# Amplifier.net
KiCad netlist of a schematic drawn in Altium Designer
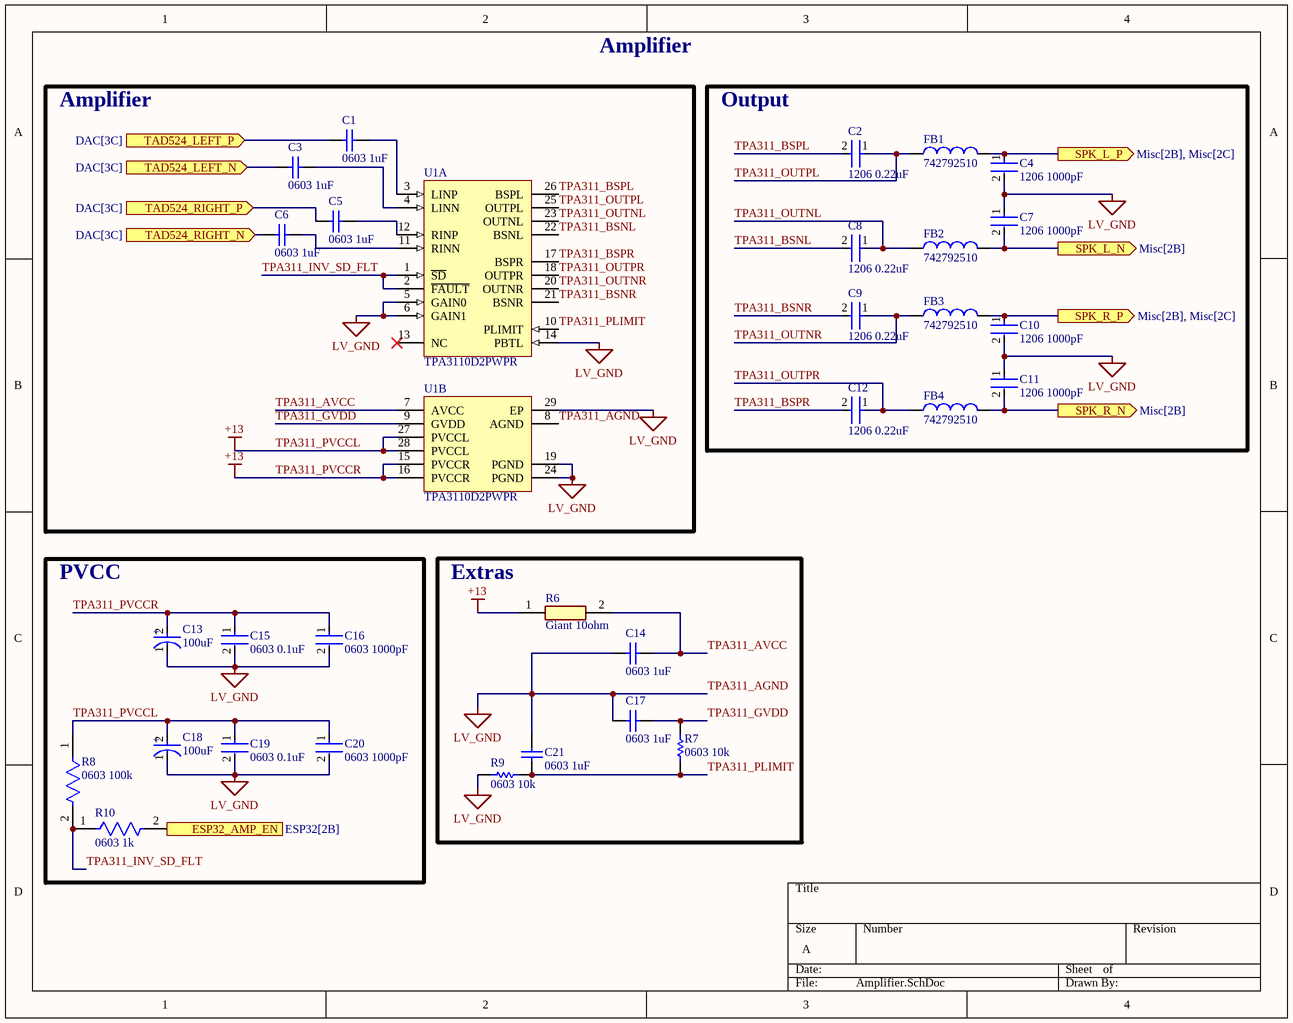
[diagram p0: Amplifier.SchDoc]

(export (version "E")
  (design (tool "Eeschema 10.0.6"))
  (components
    (comp (ref "C1")
      (value "0603 1uF")
      (footprint "CAPC1608X87X35LL15T15")
      (fields (field (name "PART NUMBER") "C0603C105K3RACTU") (field (name "MANUFACTURER") "Kemet"))
      (libsource (lib "Altium Content Vault") (part "CAP"))
    )
    (comp (ref "C2")
      (value "1206 0.22uF")
      (footprint "FP-C1206C-EB-MFG")
      (description "CAP CER 0.22UF 50V X7R 1206")
      (fields
        (field (name "OCTOPART") "https://octopart.com/c1206c224k5ractu-kemet-99129")
        (field (name "MANUFACTURER PART NUMBER") "C1206C224K5RACTU")
      )
      (libsource (lib "Altium Content Vault") (part "b4654b650e69147ec39a6b967a45e02"))
    )
    (comp (ref "C3")
      (value "0603 1uF")
      (footprint "CAPC1608X87X35LL15T15")
      (fields (field (name "PART NUMBER") "C0603C105K3RACTU") (field (name "MANUFACTURER") "Kemet"))
      (libsource (lib "Altium Content Vault") (part "CAP"))
    )
    (comp (ref "C4")
      (value "1206 1000pF")
      (footprint "FP-C1206C-EB-MFG")
      (description "CAP CER 100PF 100V C0G/NP0 1206")
      (fields (field (name "MANUFACTURER") "KEMET") (field (name "TOLERANCE") "0.05"))
      (libsource (lib "Altium Content Vault") (part "b4654b650e69147ec39a6b967a45e02"))
    )
    (comp (ref "C5")
      (value "0603 1uF")
      (footprint "CAPC1608X87X35LL15T15")
      (fields (field (name "PART NUMBER") "C0603C105K3RACTU") (field (name "MANUFACTURER") "Kemet"))
      (libsource (lib "Altium Content Vault") (part "CAP"))
    )
    (comp (ref "C6")
      (value "0603 1uF")
      (footprint "CAPC1608X87X35LL15T15")
      (fields (field (name "PART NUMBER") "C0603C105K3RACTU") (field (name "MANUFACTURER") "Kemet"))
      (libsource (lib "Altium Content Vault") (part "CAP"))
    )
    (comp (ref "C7")
      (value "1206 1000pF")
      (footprint "FP-C1206C-EB-MFG")
      (description "CAP CER 100PF 100V C0G/NP0 1206")
      (fields (field (name "MANUFACTURER") "KEMET") (field (name "TOLERANCE") "0.05"))
      (libsource (lib "Altium Content Vault") (part "b4654b650e69147ec39a6b967a45e02"))
    )
    (comp (ref "C8")
      (value "1206 0.22uF")
      (footprint "FP-C1206C-EB-MFG")
      (description "CAP CER 0.22UF 50V X7R 1206")
      (fields
        (field (name "OCTOPART") "https://octopart.com/c1206c224k5ractu-kemet-99129")
        (field (name "MANUFACTURER PART NUMBER") "C1206C224K5RACTU")
      )
      (libsource (lib "Altium Content Vault") (part "b4654b650e69147ec39a6b967a45e02"))
    )
    (comp (ref "C9")
      (value "1206 0.22uF")
      (footprint "FP-C1206C-EB-MFG")
      (description "CAP CER 0.22UF 50V X7R 1206")
      (fields
        (field (name "OCTOPART") "https://octopart.com/c1206c224k5ractu-kemet-99129")
        (field (name "MANUFACTURER PART NUMBER") "C1206C224K5RACTU")
      )
      (libsource (lib "Altium Content Vault") (part "b4654b650e69147ec39a6b967a45e02"))
    )
    (comp (ref "C10")
      (value "1206 1000pF")
      (footprint "FP-C1206C-EB-MFG")
      (description "CAP CER 100PF 100V C0G/NP0 1206")
      (fields (field (name "MANUFACTURER") "KEMET") (field (name "TOLERANCE") "0.05"))
      (libsource (lib "Altium Content Vault") (part "b4654b650e69147ec39a6b967a45e02"))
    )
    (comp (ref "C11")
      (value "1206 1000pF")
      (footprint "FP-C1206C-EB-MFG")
      (description "CAP CER 100PF 100V C0G/NP0 1206\r\nC1206C101J1GACTU")
      (fields (field (name "MANUFACTURER") "KEMET") (field (name "TOLERANCE") "0.05"))
      (libsource (lib "Altium Content Vault") (part "b4654b650e69147ec39a6b967a45e02"))
    )
    (comp (ref "C12")
      (value "1206 0.22uF")
      (footprint "FP-C1206C-EB-MFG")
      (description "CAP CER 0.22UF 50V X7R 1206")
      (fields
        (field (name "OCTOPART") "https://octopart.com/c1206c224k5ractu-kemet-99129")
        (field (name "MANUFACTURER PART NUMBER") "C1206C224K5RACTU")
      )
      (libsource (lib "Altium Content Vault") (part "b4654b650e69147ec39a6b967a45e02"))
    )
    (comp (ref "C13")
      (value "100uF")
      (footprint "FP-RAD-TH-D_8_0_5-L_11_5-MFG")
      (description "Aluminum Electrolytic Capacitors (Radial Lead Type) 100uF ±20% 50V")
      (fields (field (name "VOLTAGE") "50V") (field (name "TOLERANCE") "20%"))
      (libsource (lib "Altium Content Vault") (part "a00bbbee19879c290e62620ae7e47b1"))
    )
    (comp (ref "C14")
      (value "0603 1uF")
      (footprint "CAPC1608X87X35LL15T15")
      (fields (field (name "PART NUMBER") "C0603C105K3RACTU") (field (name "MANUFACTURER") "Kemet"))
      (libsource (lib "Altium Content Vault") (part "CAP"))
    )
    (comp (ref "C15")
      (value "0603 0.1uF")
      (footprint "FP-C0603C-CF-MFG")
      (description "CAP CER 0.1UF 25V X7R 0603")
      (fields
        (field (name "MANUFACTURER PART NUMBER") "C0603C104K3RACTU")
        (field (name "OCTOPART") "https://octopart.com/c0603c104k3ractu-kemet-127541")
      )
      (libsource (lib "Altium Content Vault") (part "b4654b650e69147ec39a6b967a45e02"))
    )
    (comp (ref "C16")
      (value "0603 1000pF")
      (footprint "FP-C0603C-CF-MFG")
      (description "CAP CER 1000PF 25V 5% NP0 0603")
      (fields
        (field (name "OCTOPART") "https://octopart.com/c0603c102j3gactu-kemet-8375722")
        (field (name "TOLERANCE") "0.05")
      )
      (libsource (lib "Altium Content Vault") (part "b4654b650e69147ec39a6b967a45e02"))
    )
    (comp (ref "C17")
      (value "0603 1uF")
      (footprint "CAPC1608X87X35LL15T15")
      (fields (field (name "PART NUMBER") "C0603C105K3RACTU") (field (name "MANUFACTURER") "Kemet"))
      (libsource (lib "Altium Content Vault") (part "CAP"))
    )
    (comp (ref "C18")
      (value "100uF")
      (footprint "FP-RAD-TH-D_8_0_5-L_11_5-MFG")
      (description "Aluminum Electrolytic Capacitors (Radial Lead Type) 100uF ±20% 50V")
      (fields (field (name "VOLTAGE") "50V") (field (name "TOLERANCE") "20%"))
      (libsource (lib "Altium Content Vault") (part "a00bbbee19879c290e62620ae7e47b1"))
    )
    (comp (ref "C19")
      (value "0603 0.1uF")
      (footprint "FP-C0603C-CF-MFG")
      (description "CAP CER 0.1UF 25V X7R 0603")
      (fields
        (field (name "MANUFACTURER PART NUMBER") "C0603C104K3RACTU")
        (field (name "OCTOPART") "https://octopart.com/c0603c104k3ractu-kemet-127541")
      )
      (libsource (lib "Altium Content Vault") (part "b4654b650e69147ec39a6b967a45e02"))
    )
    (comp (ref "C20")
      (value "0603 1000pF")
      (footprint "FP-C0603C-CF-MFG")
      (description "CAP CER 1000PF 25V 5% NP0 0603")
      (fields
        (field (name "OCTOPART") "https://octopart.com/c0603c102j3gactu-kemet-8375722")
        (field (name "TOLERANCE") "0.05")
      )
      (libsource (lib "Altium Content Vault") (part "b4654b650e69147ec39a6b967a45e02"))
    )
    (comp (ref "C21")
      (value "0603 1uF")
      (footprint "CAPC1608X87X35LL15T15")
      (fields (field (name "PART NUMBER") "C0603C105K3RACTU") (field (name "MANUFACTURER") "Kemet"))
      (libsource (lib "Altium Content Vault") (part "CAP"))
    )
    (comp (ref "FB1")
      (value "742792510")
      (footprint "WE-CBF_1812_L4.5W3.2H1.5_HC")
      (fields (field (name "TOLERANCE") "25%"))
      (libsource (lib "Altium Content Vault") (part "Ferrite"))
    )
    (comp (ref "FB2")
      (value "742792510")
      (footprint "WE-CBF_1812_L4.5W3.2H1.5_HC")
      (fields (field (name "TOLERANCE") "25%"))
      (libsource (lib "Altium Content Vault") (part "Ferrite"))
    )
    (comp (ref "FB3")
      (value "742792510")
      (footprint "WE-CBF_1812_L4.5W3.2H1.5_HC")
      (fields (field (name "TOLERANCE") "25%"))
      (libsource (lib "Altium Content Vault") (part "Ferrite"))
    )
    (comp (ref "FB4")
      (value "742792510")
      (footprint "WE-CBF_1812_L4.5W3.2H1.5_HC")
      (fields (field (name "TOLERANCE") "25%"))
      (libsource (lib "Altium Content Vault") (part "Ferrite"))
    )
    (comp (ref "R6")
      (value "Giant 10ohm")
      (footprint "SamacSys:TO508P350X1040X2030-2P")
      (description "Resistor")
      (fields
        (field (name "MANUFACTURER_PART_NUMBER") "LTO050F10R00JTE3")
        (field (name "MOUSER PART NUMBER") "72-LTO050F10R00JTE3")
      )
      (libsource (lib "*") (part "LTO050F10R00JTE3"))
    )
    (comp (ref "R7")
      (value "0603 10k")
      (footprint "RESC1609X55X30LL15T15")
      (description "Chip Resistor, 10 KOhm, +/- 1%, 0.1 W, -55 to 155 degC, 0603 (1608 Metric), RoHS, Tape and Reel")
      (fields (field (name "TOLERANCE") "1%") (field (name "MANUFACTURER") "Panasonic"))
      (libsource (lib "Altium Content Vault") (part "RES-2"))
    )
    (comp (ref "R8")
      (value "0603 100k")
      (footprint "FP-RC0603-0_55-MFG")
      (description "RES SMD 100K OHM 1% 1/10W 0603")
      (fields (field (name "TOLERANCE") "1%"))
      (libsource (lib "Altium Content Vault") (part "1029c3af85768c4190bb7ad29bc67b5"))
    )
    (comp (ref "R9")
      (value "0603 10k")
      (footprint "RESC1609X55X30LL15T15")
      (description "Chip Resistor, 10 KOhm, +/- 1%, 0.1 W, -55 to 155 degC, 0603 (1608 Metric), RoHS, Tape and Reel")
      (fields (field (name "TOLERANCE") "1%") (field (name "MANUFACTURER") "Panasonic"))
      (libsource (lib "Altium Content Vault") (part "RES-2"))
    )
    (comp (ref "R10")
      (value "0603 1k")
      (footprint "FP-AC0603-IPC_B")
      (description "RES 1kΩ 1.00% 0.1W 0603")
      (fields (field (name "TOLERANCE") "1%"))
      (libsource (lib "Altium Content Vault") (part "1029c3af85768c4190bb7ad29bc67b5"))
    )
    (comp (ref "U1")
      (value "TPA3110D2PWPR")
      (footprint "TI-PWP28-5720X1950TP_L")
      (fields (field (name "MANUFACTURER") "Texas Instruments"))
      (libsource (lib "Altium Content Vault") (part "TI-TPA311XD2PWP28-6240X1950TP"))
    )
  )
  (nets
    (net (code "1") (name "+13") (class "Default")
      (node (ref "C13") (pin "2") (pinfunction "A_2") (pintype "passive"))
      (node (ref "C15") (pin "1") (pinfunction "1_1") (pintype "passive"))
      (node (ref "C16") (pin "1") (pinfunction "1_1") (pintype "passive"))
      (node (ref "C18") (pin "2") (pinfunction "A_2") (pintype "passive"))
      (node (ref "C19") (pin "1") (pinfunction "1_1") (pintype "passive"))
      (node (ref "C20") (pin "1") (pinfunction "1_1") (pintype "passive"))
      (node (ref "R6") (pin "1") (pinfunction "1_1") (pintype "passive"))
      (node (ref "R8") (pin "1") (pinfunction "1_1") (pintype "passive"))
      (node (ref "U1") (pin "15") (pinfunction "PVCCR_15") (pintype "power_in"))
      (node (ref "U1") (pin "16") (pinfunction "PVCCR_16") (pintype "power_in"))
      (node (ref "U1") (pin "27") (pinfunction "PVCCL_27") (pintype "power_in"))
      (node (ref "U1") (pin "28") (pinfunction "PVCCL_28") (pintype "power_in"))
    )
    (net (code "2") (name "/ESP32_AMP_EN") (class "Default")
      (node (ref "R10") (pin "2") (pinfunction "2_2") (pintype "passive"))
    )
    (net (code "3") (name "/SPK_L_N") (class "Default")
      (node (ref "C7") (pin "2") (pinfunction "2_2") (pintype "passive"))
      (node (ref "FB2") (pin "2") (pinfunction "2_2") (pintype "passive"))
    )
    (net (code "4") (name "/SPK_L_P") (class "Default")
      (node (ref "C4") (pin "1") (pinfunction "1_1") (pintype "passive"))
      (node (ref "FB1") (pin "2") (pinfunction "2_2") (pintype "passive"))
    )
    (net (code "5") (name "/SPK_R_N") (class "Default")
      (node (ref "C11") (pin "2") (pinfunction "2_2") (pintype "passive"))
      (node (ref "FB4") (pin "2") (pinfunction "2_2") (pintype "passive"))
    )
    (net (code "6") (name "/SPK_R_P") (class "Default")
      (node (ref "C10") (pin "1") (pinfunction "1_1") (pintype "passive"))
      (node (ref "FB3") (pin "2") (pinfunction "2_2") (pintype "passive"))
    )
    (net (code "7") (name "/TAD524_LEFT_N") (class "Default")
      (node (ref "C3") (pin "1") (pinfunction "1_1") (pintype "passive"))
    )
    (net (code "8") (name "/TAD524_LEFT_P") (class "Default")
      (node (ref "C1") (pin "1") (pinfunction "1_1") (pintype "passive"))
    )
    (net (code "9") (name "/TAD524_RIGHT_N") (class "Default")
      (node (ref "C6") (pin "1") (pinfunction "1_1") (pintype "passive"))
    )
    (net (code "10") (name "/TAD524_RIGHT_P") (class "Default")
      (node (ref "C5") (pin "1") (pinfunction "1_1") (pintype "passive"))
    )
    (net (code "11") (name "/TPA311_AVCC") (class "Default")
      (node (ref "C14") (pin "2") (pinfunction "2_2") (pintype "passive"))
      (node (ref "R6") (pin "2") (pinfunction "2_2") (pintype "passive"))
      (node (ref "U1") (pin "7") (pinfunction "AVCC_7") (pintype "power_in"))
    )
    (net (code "12") (name "/TPA311_BSNL") (class "Default")
      (node (ref "C8") (pin "2") (pinfunction "2_2") (pintype "passive"))
      (node (ref "U1") (pin "22") (pinfunction "BSNL_22") (pintype "passive"))
    )
    (net (code "13") (name "/TPA311_BSNR") (class "Default")
      (node (ref "C9") (pin "2") (pinfunction "2_2") (pintype "passive"))
      (node (ref "U1") (pin "21") (pinfunction "BSNR_21") (pintype "passive"))
    )
    (net (code "14") (name "/TPA311_BSPL") (class "Default")
      (node (ref "C2") (pin "2") (pinfunction "2_2") (pintype "passive"))
      (node (ref "U1") (pin "26") (pinfunction "BSPL_26") (pintype "passive"))
    )
    (net (code "15") (name "/TPA311_BSPR") (class "Default")
      (node (ref "C12") (pin "2") (pinfunction "2_2") (pintype "passive"))
      (node (ref "U1") (pin "17") (pinfunction "BSPR_17") (pintype "passive"))
    )
    (net (code "16") (name "/TPA311_GVDD") (class "Default")
      (node (ref "C17") (pin "2") (pinfunction "2_2") (pintype "passive"))
      (node (ref "R7") (pin "1") (pinfunction "1_1") (pintype "passive"))
      (node (ref "U1") (pin "9") (pinfunction "GVDD_9") (pintype "power_in"))
    )
    (net (code "17") (name "/TPA311_INV_SD_FLT") (class "Default")
      (node (ref "R10") (pin "1") (pinfunction "1_1") (pintype "passive"))
      (node (ref "R8") (pin "2") (pinfunction "2_2") (pintype "passive"))
      (node (ref "U1") (pin "1") (pinfunction "~{SD}_1") (pintype "input"))
      (node (ref "U1") (pin "2") (pinfunction "~{FAULT}_2") (pintype "open_collector"))
    )
    (net (code "18") (name "/TPA311_OUTNL") (class "Default")
      (node (ref "C8") (pin "1") (pinfunction "1_1") (pintype "passive"))
      (node (ref "FB2") (pin "1") (pinfunction "1_1") (pintype "passive"))
      (node (ref "U1") (pin "23") (pinfunction "OUTNL_23") (pintype "tri_state"))
    )
    (net (code "19") (name "/TPA311_OUTNR") (class "Default")
      (node (ref "C9") (pin "1") (pinfunction "1_1") (pintype "passive"))
      (node (ref "FB3") (pin "1") (pinfunction "1_1") (pintype "passive"))
      (node (ref "U1") (pin "20") (pinfunction "OUTNR_20") (pintype "tri_state"))
    )
    (net (code "20") (name "/TPA311_OUTPL") (class "Default")
      (node (ref "C2") (pin "1") (pinfunction "1_1") (pintype "passive"))
      (node (ref "FB1") (pin "1") (pinfunction "1_1") (pintype "passive"))
      (node (ref "U1") (pin "25") (pinfunction "OUTPL_25") (pintype "tri_state"))
    )
    (net (code "21") (name "/TPA311_OUTPR") (class "Default")
      (node (ref "C12") (pin "1") (pinfunction "1_1") (pintype "passive"))
      (node (ref "FB4") (pin "1") (pinfunction "1_1") (pintype "passive"))
      (node (ref "U1") (pin "18") (pinfunction "OUTPR_18") (pintype "tri_state"))
    )
    (net (code "22") (name "/TPA311_PLIMIT") (class "Default")
      (node (ref "C21") (pin "2") (pinfunction "2_2") (pintype "passive"))
      (node (ref "R7") (pin "2") (pinfunction "2_2") (pintype "passive"))
      (node (ref "R9") (pin "2") (pinfunction "2_2") (pintype "passive"))
      (node (ref "U1") (pin "10") (pinfunction "PLIMIT_10") (pintype "input"))
    )
    (net (code "23") (name "LV_GND") (class "Default")
      (node (ref "C10") (pin "2") (pinfunction "2_2") (pintype "passive"))
      (node (ref "C11") (pin "1") (pinfunction "1_1") (pintype "passive"))
      (node (ref "C13") (pin "1") (pinfunction "C_1") (pintype "passive"))
      (node (ref "C14") (pin "1") (pinfunction "1_1") (pintype "passive"))
      (node (ref "C15") (pin "2") (pinfunction "2_2") (pintype "passive"))
      (node (ref "C16") (pin "2") (pinfunction "2_2") (pintype "passive"))
      (node (ref "C17") (pin "1") (pinfunction "1_1") (pintype "passive"))
      (node (ref "C18") (pin "1") (pinfunction "C_1") (pintype "passive"))
      (node (ref "C19") (pin "2") (pinfunction "2_2") (pintype "passive"))
      (node (ref "C20") (pin "2") (pinfunction "2_2") (pintype "passive"))
      (node (ref "C21") (pin "1") (pinfunction "1_1") (pintype "passive"))
      (node (ref "C4") (pin "2") (pinfunction "2_2") (pintype "passive"))
      (node (ref "C7") (pin "1") (pinfunction "1_1") (pintype "passive"))
      (node (ref "R9") (pin "1") (pinfunction "1_1") (pintype "passive"))
      (node (ref "U1") (pin "14") (pinfunction "PBTL_14") (pintype "input"))
      (node (ref "U1") (pin "19") (pinfunction "PGND_19") (pintype "power_in"))
      (node (ref "U1") (pin "24") (pinfunction "PGND_24") (pintype "power_in"))
      (node (ref "U1") (pin "29") (pinfunction "EP_29") (pintype "power_in"))
      (node (ref "U1") (pin "5") (pinfunction "GAIN0_5") (pintype "input"))
      (node (ref "U1") (pin "6") (pinfunction "GAIN1_6") (pintype "input"))
      (node (ref "U1") (pin "8") (pinfunction "AGND_8") (pintype "power_in"))
    )
    (net (code "24") (name "Net-(U1A-LINN)") (class "Default")
      (node (ref "C3") (pin "2") (pinfunction "2_2") (pintype "passive"))
      (node (ref "U1") (pin "4") (pinfunction "LINN_4") (pintype "input"))
    )
    (net (code "25") (name "Net-(U1A-LINP)") (class "Default")
      (node (ref "C1") (pin "2") (pinfunction "2_2") (pintype "passive"))
      (node (ref "U1") (pin "3") (pinfunction "LINP_3") (pintype "input"))
    )
    (net (code "26") (name "Net-(U1A-RINN)") (class "Default")
      (node (ref "C6") (pin "2") (pinfunction "2_2") (pintype "passive"))
      (node (ref "U1") (pin "11") (pinfunction "RINN_11") (pintype "input"))
    )
    (net (code "27") (name "Net-(U1A-RINP)") (class "Default")
      (node (ref "C5") (pin "2") (pinfunction "2_2") (pintype "passive"))
      (node (ref "U1") (pin "12") (pinfunction "RINP_12") (pintype "input"))
    )
    (net (code "28") (name "unconnected-(U1A-NC-Pad13)") (class "Default")
      (node (ref "U1") (pin "13") (pinfunction "NC_13") (pintype "passive+no_connect"))
    )
  )
)
